# 9_12.net
KiCad netlist of a schematic drawn in Altium Designer
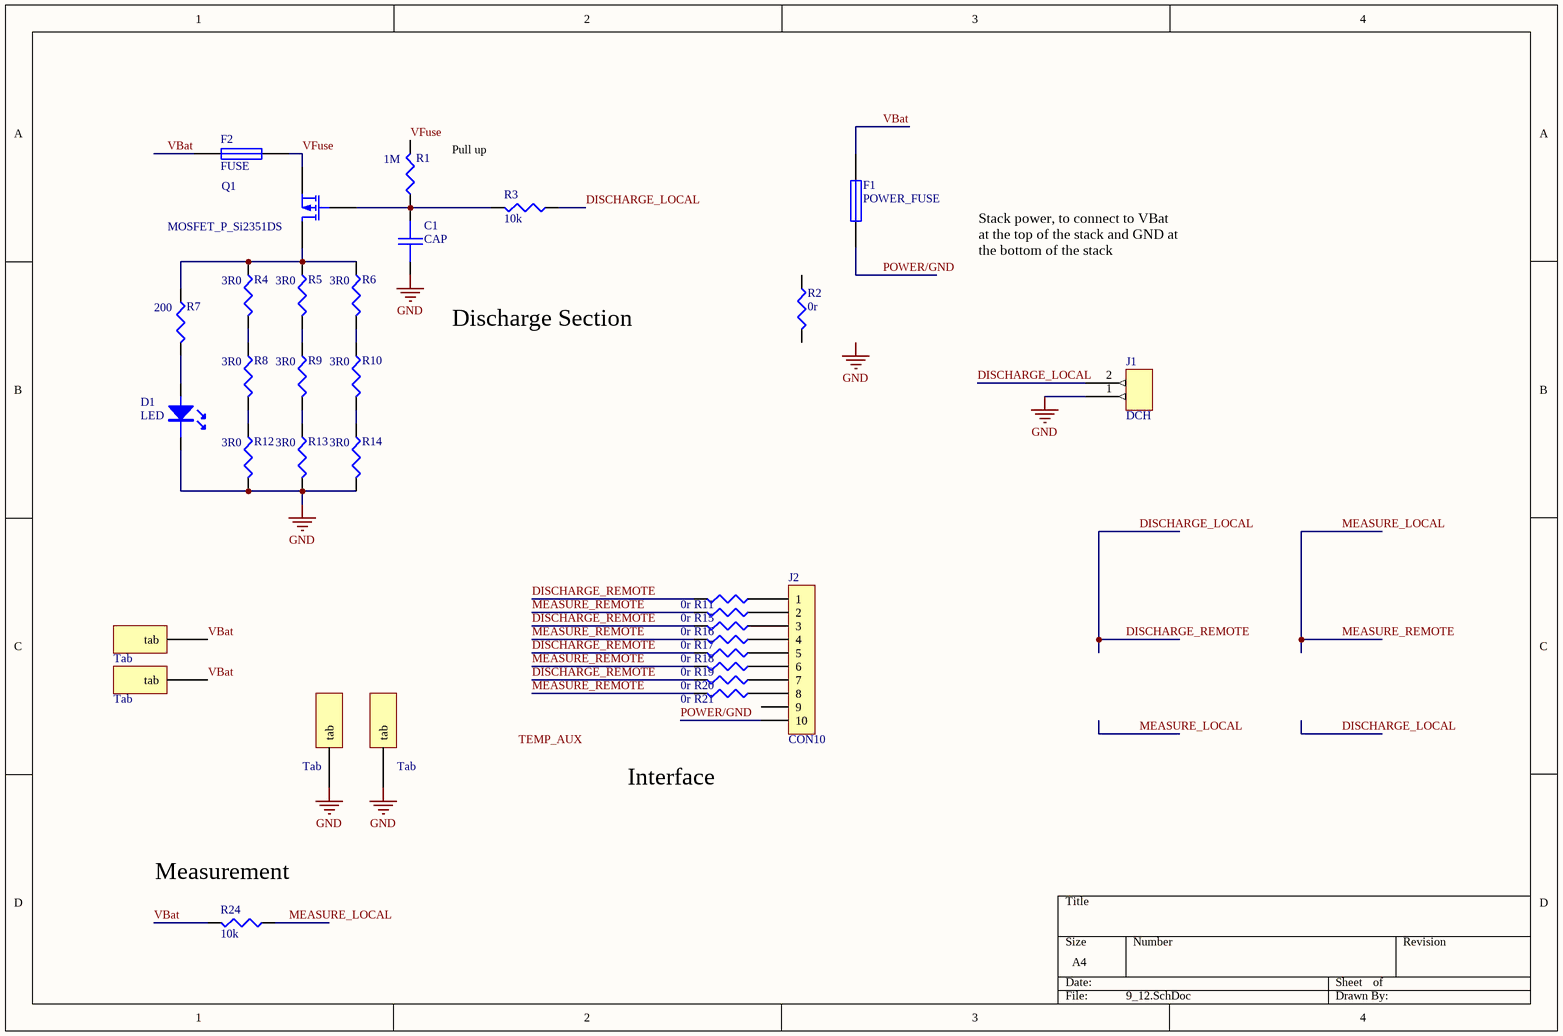
[diagram p0: 9_12.SchDoc]

(export (version "E")
  (design (tool "Eeschema 10.0.6"))
  (components
    (comp (ref "C1")
      (value "CAP")
      (footprint "0603")
      (description "Capacitor")
      (libsource (lib "RCLDQ") (part "CAP"))
    )
    (comp (ref "D1") (value "LED") (footprint "0805LED") (libsource (lib "RCLDQ") (part "LED")))
    (comp (ref "F1")
      (value "POWER_FUSE")
      (footprint "1210")
      (description "Fuse")
      (libsource (lib "Miscellaneous") (part "FUSE"))
    )
    (comp (ref "F2")
      (value "FUSE")
      (footprint "LITTELFUSE-154")
      (description "Fuse")
      (libsource (lib "Miscellaneous") (part "FUSE"))
    )
    (comp (ref "J1") (value "DCH") (footprint "IDC2") (libsource (lib "Connectors") (part "CON2")))
    (comp (ref "J2")
      (value "CON10")
      (footprint "IDC10")
      (description "10 pin, right angle, ribbon con with claws")
      (libsource (lib "Connectors") (part "CON10"))
    )
    (comp (ref "J4") (value "Tab") (footprint "tab_connect") (libsource (lib "BMS") (part "tab_connection")))
    (comp (ref "J5") (value "Tab") (footprint "tab_connect") (libsource (lib "BMS") (part "tab_connection")))
    (comp (ref "J6") (value "Tab") (footprint "tab_connect") (libsource (lib "") (part "tab_connection_1")))
    (comp (ref "J7") (value "Tab") (footprint "tab_connect") (libsource (lib "") (part "tab_connection_1")))
    (comp (ref "Q1")
      (value "MOSFET_P_Si2351DS")
      (footprint "SOT23-3")
      (description "Si2351DS P-Channel MOSFET")
      (fields (field (name "PUBLISHER") "Altium Limited"))
      (libsource (lib "RCLDQ") (part "MOSFET_P_Si2351DS"))
    )
    (comp (ref "R1")
      (value "~")
      (footprint "0603")
      (description "Resistor")
      (fields (field (name "RESISTANCE") "1M"))
      (libsource (lib "RCLDQ") (part "RES1"))
    )
    (comp (ref "R2")
      (value "~")
      (footprint "1206")
      (description "Resistor")
      (fields (field (name "RESISTANCE") "0r"))
      (libsource (lib "RCLDQ") (part "RES1"))
    )
    (comp (ref "R3")
      (value "~")
      (footprint "0603")
      (description "Resistor")
      (fields (field (name "RESISTANCE") "10k"))
      (libsource (lib "RCLDQ") (part "RES1"))
    )
    (comp (ref "R4")
      (value "3R0")
      (footprint "2512")
      (description "Resistor")
      (libsource (lib "RCLDQ") (part "RES1"))
    )
    (comp (ref "R5")
      (value "3R0")
      (footprint "2512")
      (description "Resistor")
      (libsource (lib "RCLDQ") (part "RES1"))
    )
    (comp (ref "R6")
      (value "3R0")
      (footprint "2512")
      (description "Resistor")
      (libsource (lib "RCLDQ") (part "RES1"))
    )
    (comp (ref "R7")
      (value "200")
      (footprint "0603")
      (description "Resistor")
      (libsource (lib "RCLDQ") (part "RES1"))
    )
    (comp (ref "R8")
      (value "3R0")
      (footprint "2512")
      (description "Resistor")
      (libsource (lib "RCLDQ") (part "RES1"))
    )
    (comp (ref "R9")
      (value "3R0")
      (footprint "2512")
      (description "Resistor")
      (libsource (lib "RCLDQ") (part "RES1"))
    )
    (comp (ref "R10")
      (value "3R0")
      (footprint "2512")
      (description "Resistor")
      (libsource (lib "RCLDQ") (part "RES1"))
    )
    (comp (ref "R11")
      (value "~")
      (footprint "0603")
      (description "Resistor")
      (fields (field (name "RESISTANCE") "0r"))
      (libsource (lib "RCLDQ") (part "RES1"))
    )
    (comp (ref "R12")
      (value "3R0")
      (footprint "2512")
      (description "Resistor")
      (libsource (lib "RCLDQ") (part "RES1"))
    )
    (comp (ref "R13")
      (value "3R0")
      (footprint "2512")
      (description "Resistor")
      (libsource (lib "RCLDQ") (part "RES1"))
    )
    (comp (ref "R14")
      (value "3R0")
      (footprint "2512")
      (description "Resistor")
      (libsource (lib "RCLDQ") (part "RES1"))
    )
    (comp (ref "R15")
      (value "~")
      (footprint "0603")
      (description "Resistor")
      (fields (field (name "RESISTANCE") "0r"))
      (libsource (lib "RCLDQ") (part "RES1"))
    )
    (comp (ref "R16")
      (value "~")
      (footprint "0603")
      (description "Resistor")
      (fields (field (name "RESISTANCE") "0r"))
      (libsource (lib "RCLDQ") (part "RES1"))
    )
    (comp (ref "R17")
      (value "~")
      (footprint "0603")
      (description "Resistor")
      (fields (field (name "RESISTANCE") "0r"))
      (libsource (lib "RCLDQ") (part "RES1"))
    )
    (comp (ref "R18")
      (value "~")
      (footprint "0603")
      (description "Resistor")
      (fields (field (name "RESISTANCE") "0r"))
      (libsource (lib "RCLDQ") (part "RES1"))
    )
    (comp (ref "R19")
      (value "~")
      (footprint "0603")
      (description "Resistor")
      (fields (field (name "RESISTANCE") "0r"))
      (libsource (lib "RCLDQ") (part "RES1"))
    )
    (comp (ref "R20")
      (value "~")
      (footprint "0603")
      (description "Resistor")
      (fields (field (name "RESISTANCE") "0r"))
      (libsource (lib "RCLDQ") (part "RES1"))
    )
    (comp (ref "R21")
      (value "~")
      (footprint "0603")
      (description "Resistor")
      (fields (field (name "RESISTANCE") "0r"))
      (libsource (lib "RCLDQ") (part "RES1"))
    )
    (comp (ref "R24")
      (value "~")
      (footprint "0603")
      (description "Resistor")
      (fields (field (name "RESISTANCE") "10k"))
      (libsource (lib "RCLDQ") (part "RES1"))
    )
  )
  (nets
    (net (code "1") (name "/DISCHARGE_LOCAL") (class "Default")
      (node (ref "J1") (pin "2") (pinfunction "2_2") (pintype "output"))
      (node (ref "R11") (pin "2") (pinfunction "2_2") (pintype "passive"))
      (node (ref "R16") (pin "2") (pinfunction "2_2") (pintype "passive"))
      (node (ref "R18") (pin "2") (pinfunction "2_2") (pintype "passive"))
      (node (ref "R20") (pin "2") (pinfunction "2_2") (pintype "passive"))
      (node (ref "R3") (pin "1") (pinfunction "1_1") (pintype "passive"))
    )
    (net (code "2") (name "/MEASURE_LOCAL") (class "Default")
      (node (ref "R15") (pin "2") (pinfunction "2_2") (pintype "passive"))
      (node (ref "R17") (pin "2") (pinfunction "2_2") (pintype "passive"))
      (node (ref "R19") (pin "2") (pinfunction "2_2") (pintype "passive"))
      (node (ref "R21") (pin "2") (pinfunction "2_2") (pintype "passive"))
      (node (ref "R24") (pin "1") (pinfunction "1_1") (pintype "passive"))
    )
    (net (code "3") (name "/POWER{slash}GND") (class "Default")
      (node (ref "F1") (pin "1") (pinfunction "1_1") (pintype "passive"))
      (node (ref "J2") (pin "10") (pinfunction "10_10") (pintype "passive"))
    )
    (net (code "5") (name "/VBat") (class "Default")
      (node (ref "F1") (pin "2") (pinfunction "2_2") (pintype "passive"))
      (node (ref "F2") (pin "1") (pinfunction "1_1") (pintype "passive"))
      (node (ref "J4") (pin "0") (pinfunction "tab_0") (pintype "passive"))
      (node (ref "J5") (pin "0") (pinfunction "tab_0") (pintype "passive"))
      (node (ref "R24") (pin "2") (pinfunction "2_2") (pintype "passive"))
    )
    (net (code "6") (name "/VFuse") (class "Default")
      (node (ref "F2") (pin "2") (pinfunction "2_2") (pintype "passive"))
      (node (ref "Q1") (pin "2") (pinfunction "S_2") (pintype "passive"))
      (node (ref "R1") (pin "2") (pinfunction "2_2") (pintype "passive"))
    )
    (net (code "7") (name "GND") (class "Default")
      (node (ref "C1") (pin "2") (pinfunction "2_2") (pintype "passive"))
      (node (ref "D1") (pin "K") (pinfunction "K_K") (pintype "passive"))
      (node (ref "J1") (pin "1") (pinfunction "1_1") (pintype "output"))
      (node (ref "J6") (pin "0") (pinfunction "tab_0") (pintype "passive"))
      (node (ref "J7") (pin "0") (pinfunction "tab_0") (pintype "passive"))
      (node (ref "R12") (pin "2") (pinfunction "2_2") (pintype "passive"))
      (node (ref "R13") (pin "2") (pinfunction "2_2") (pintype "passive"))
      (node (ref "R14") (pin "2") (pinfunction "2_2") (pintype "passive"))
    )
    (net (code "8") (name "Net-(D1-PadA)") (class "Default")
      (node (ref "D1") (pin "A") (pinfunction "A_A") (pintype "passive"))
      (node (ref "R7") (pin "2") (pinfunction "2_2") (pintype "passive"))
    )
    (net (code "9") (name "Net-(J2-Pad1)") (class "Default")
      (node (ref "J2") (pin "1") (pinfunction "1_1") (pintype "passive"))
      (node (ref "R11") (pin "1") (pinfunction "1_1") (pintype "passive"))
    )
    (net (code "10") (name "Net-(J2-Pad2)") (class "Default")
      (node (ref "J2") (pin "2") (pinfunction "2_2") (pintype "passive"))
      (node (ref "R15") (pin "1") (pinfunction "1_1") (pintype "passive"))
    )
    (net (code "11") (name "Net-(J2-Pad3)") (class "Default")
      (node (ref "J2") (pin "3") (pinfunction "3_3") (pintype "passive"))
      (node (ref "R16") (pin "1") (pinfunction "1_1") (pintype "passive"))
    )
    (net (code "12") (name "Net-(J2-Pad4)") (class "Default")
      (node (ref "J2") (pin "4") (pinfunction "4_4") (pintype "passive"))
      (node (ref "R17") (pin "1") (pinfunction "1_1") (pintype "passive"))
    )
    (net (code "13") (name "Net-(J2-Pad5)") (class "Default")
      (node (ref "J2") (pin "5") (pinfunction "5_5") (pintype "passive"))
      (node (ref "R18") (pin "1") (pinfunction "1_1") (pintype "passive"))
    )
    (net (code "14") (name "Net-(J2-Pad6)") (class "Default")
      (node (ref "J2") (pin "6") (pinfunction "6_6") (pintype "passive"))
      (node (ref "R19") (pin "1") (pinfunction "1_1") (pintype "passive"))
    )
    (net (code "15") (name "Net-(J2-Pad7)") (class "Default")
      (node (ref "J2") (pin "7") (pinfunction "7_7") (pintype "passive"))
      (node (ref "R20") (pin "1") (pinfunction "1_1") (pintype "passive"))
    )
    (net (code "16") (name "Net-(J2-Pad8)") (class "Default")
      (node (ref "J2") (pin "8") (pinfunction "8_8") (pintype "passive"))
      (node (ref "R21") (pin "1") (pinfunction "1_1") (pintype "passive"))
    )
    (net (code "17") (name "Net-(Q1-D)") (class "Default")
      (node (ref "Q1") (pin "3") (pinfunction "D_3") (pintype "passive"))
      (node (ref "R4") (pin "1") (pinfunction "1_1") (pintype "passive"))
      (node (ref "R5") (pin "1") (pinfunction "1_1") (pintype "passive"))
      (node (ref "R6") (pin "1") (pinfunction "1_1") (pintype "passive"))
      (node (ref "R7") (pin "1") (pinfunction "1_1") (pintype "passive"))
    )
    (net (code "18") (name "Net-(Q1-G)") (class "Default")
      (node (ref "C1") (pin "1") (pinfunction "1_1") (pintype "passive"))
      (node (ref "Q1") (pin "1") (pinfunction "G_1") (pintype "passive"))
      (node (ref "R1") (pin "1") (pinfunction "1_1") (pintype "passive"))
      (node (ref "R3") (pin "2") (pinfunction "2_2") (pintype "passive"))
    )
    (net (code "19") (name "Net-(R4-Pad2)") (class "Default")
      (node (ref "R4") (pin "2") (pinfunction "2_2") (pintype "passive"))
      (node (ref "R8") (pin "1") (pinfunction "1_1") (pintype "passive"))
    )
    (net (code "20") (name "Net-(R5-Pad2)") (class "Default")
      (node (ref "R5") (pin "2") (pinfunction "2_2") (pintype "passive"))
      (node (ref "R9") (pin "1") (pinfunction "1_1") (pintype "passive"))
    )
    (net (code "21") (name "Net-(R10-Pad1)") (class "Default")
      (node (ref "R10") (pin "1") (pinfunction "1_1") (pintype "passive"))
      (node (ref "R6") (pin "2") (pinfunction "2_2") (pintype "passive"))
    )
    (net (code "22") (name "Net-(R10-Pad2)") (class "Default")
      (node (ref "R10") (pin "2") (pinfunction "2_2") (pintype "passive"))
      (node (ref "R14") (pin "1") (pinfunction "1_1") (pintype "passive"))
    )
    (net (code "23") (name "Net-(R12-Pad1)") (class "Default")
      (node (ref "R12") (pin "1") (pinfunction "1_1") (pintype "passive"))
      (node (ref "R8") (pin "2") (pinfunction "2_2") (pintype "passive"))
    )
    (net (code "24") (name "Net-(R13-Pad1)") (class "Default")
      (node (ref "R13") (pin "1") (pinfunction "1_1") (pintype "passive"))
      (node (ref "R9") (pin "2") (pinfunction "2_2") (pintype "passive"))
    )
    (net (code "25") (name "unconnected-(J2-Pad9)") (class "Default")
      (node (ref "J2") (pin "9") (pinfunction "9_9") (pintype "passive"))
    )
    (net (code "26") (name "unconnected-(R2-Pad1)") (class "Default")
      (node (ref "R2") (pin "1") (pinfunction "1_1") (pintype "passive"))
    )
    (net (code "27") (name "unconnected-(R2-Pad2)") (class "Default")
      (node (ref "R2") (pin "2") (pinfunction "2_2") (pintype "passive"))
    )
  )
)
